# Arduino.net
KiCad netlist of a schematic drawn in Altium Designer
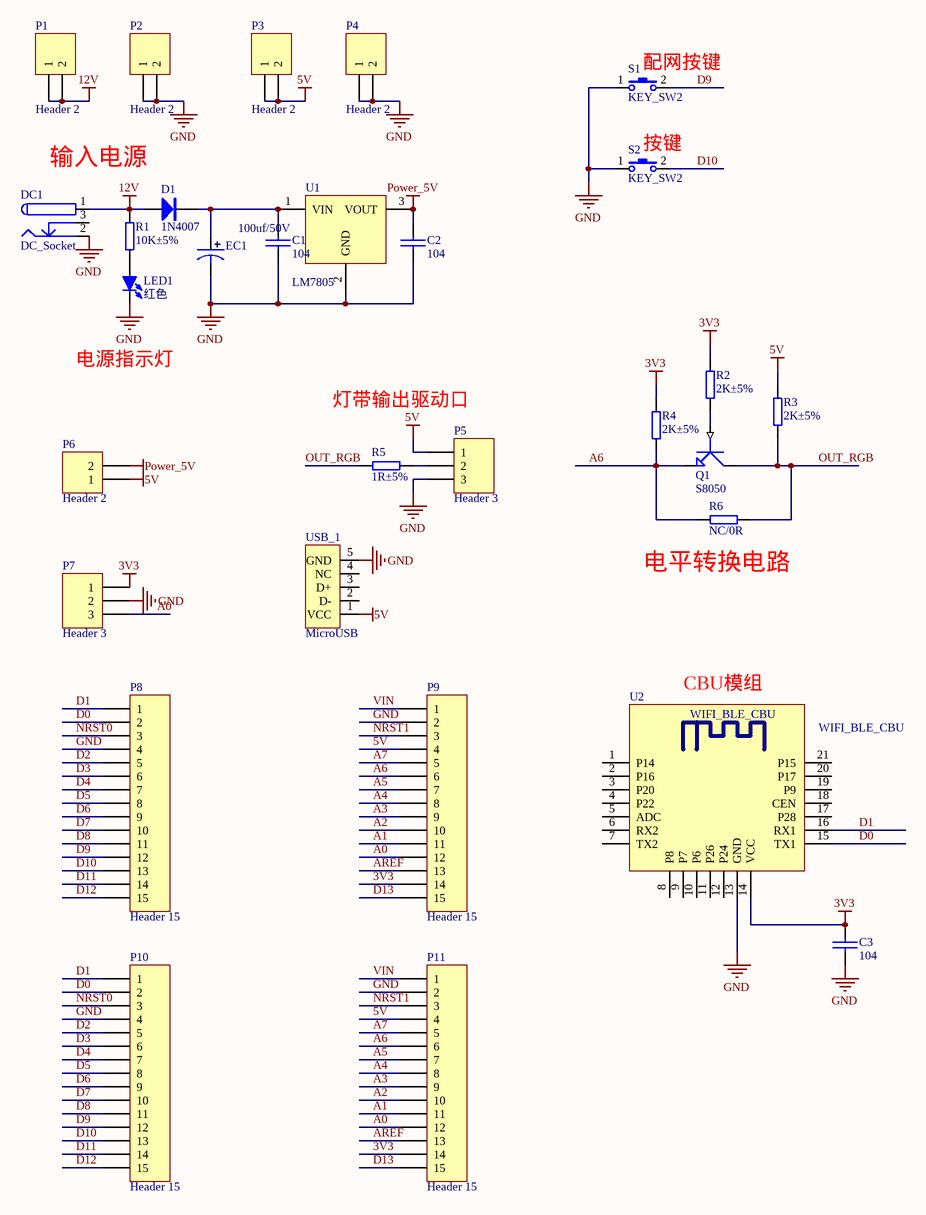
[diagram p0: Arduino幻彩灯带.SchDoc]

(export (version "E")
  (design (tool "Eeschema 10.0.6"))
  (components
    (comp (ref "C1")
      (value "104")
      (footprint "0805C")
      (description "无极性电容")
      (libsource (lib "电容") (part "CAP"))
    )
    (comp (ref "C2")
      (value "104")
      (footprint "0805C")
      (description "无极性电容")
      (libsource (lib "电容") (part "CAP"))
    )
    (comp (ref "C3")
      (value "104")
      (footprint "0805C")
      (description "无极性电容")
      (libsource (lib "电容") (part "CAP"))
    )
    (comp (ref "D1")
      (value "1N4007")
      (footprint "SMA")
      (description "整流二极管")
      (libsource (lib "二极管-整流桥") (part "1N4007"))
    )
    (comp (ref "DC1") (value "DC_Socket") (footprint "DC-005") (libsource (lib "电源插座") (part "DC_Socket")))
    (comp (ref "EC1")
      (value "100uf/50V")
      (footprint "DIP-EC3.5X8X11.5")
      (description "直插电解电容")
      (libsource (lib "电容") (part "DIP_ECAP"))
    )
    (comp (ref "LED1")
      (value "红色")
      (footprint "LED 0603R")
      (description "贴片LED")
      (libsource (lib "LED") (part "LED-SMD"))
    )
    (comp (ref "P1")
      (value "Header 2")
      (footprint "HDR1X2")
      (description "Header, 2-Pin")
      (fields (field (name "PUBLISHER") "Altium Limited"))
      (libsource (lib "Miscellaneous Connectors") (part "Header 2"))
    )
    (comp (ref "P2")
      (value "Header 2")
      (footprint "HDR1X2")
      (description "Header, 2-Pin")
      (fields (field (name "PUBLISHER") "Altium Limited"))
      (libsource (lib "Miscellaneous Connectors") (part "Header 2"))
    )
    (comp (ref "P3")
      (value "Header 2")
      (footprint "HDR1X2")
      (description "Header, 2-Pin")
      (fields (field (name "PUBLISHER") "Altium Limited"))
      (libsource (lib "Miscellaneous Connectors") (part "Header 2"))
    )
    (comp (ref "P4")
      (value "Header 2")
      (footprint "HDR1X2")
      (description "Header, 2-Pin")
      (fields (field (name "PUBLISHER") "Altium Limited"))
      (libsource (lib "Miscellaneous Connectors") (part "Header 2"))
    )
    (comp (ref "P5")
      (value "Header 3")
      (footprint "HDR1X3")
      (description "Header, 3-Pin")
      (fields (field (name "PUBLISHER") "Altium Limited"))
      (libsource (lib "Miscellaneous Connectors") (part "Header 3"))
    )
    (comp (ref "P6")
      (value "Header 2")
      (footprint "HDR1X2")
      (description "Header, 2-Pin")
      (fields (field (name "PUBLISHER") "Altium Limited"))
      (libsource (lib "") (part "Header 2_1"))
    )
    (comp (ref "P7")
      (value "Header 3")
      (footprint "HDR1X3")
      (description "Header, 3-Pin")
      (fields (field (name "PUBLISHER") "Altium Limited"))
      (libsource (lib "") (part "Header 3_1"))
    )
    (comp (ref "P8")
      (value "Header 15")
      (footprint "HDR1X15")
      (description "Header, 15-Pin")
      (fields (field (name "PUBLISHER") "Altium Limited"))
      (libsource (lib "Miscellaneous Connectors") (part "Header 15"))
    )
    (comp (ref "P9")
      (value "Header 15")
      (footprint "HDR1X15")
      (description "Header, 15-Pin")
      (fields (field (name "PUBLISHER") "Altium Limited"))
      (libsource (lib "Miscellaneous Connectors") (part "Header 15"))
    )
    (comp (ref "P10")
      (value "Header 15")
      (footprint "HDR1X15")
      (description "Header, 15-Pin")
      (fields (field (name "PUBLISHER") "Altium Limited"))
      (libsource (lib "Miscellaneous Connectors") (part "Header 15"))
    )
    (comp (ref "P11")
      (value "Header 15")
      (footprint "HDR1X15")
      (description "Header, 15-Pin")
      (fields (field (name "PUBLISHER") "Altium Limited"))
      (libsource (lib "Miscellaneous Connectors") (part "Header 15"))
    )
    (comp (ref "Q1")
      (value "S8050")
      (footprint "SOT-23-NPN")
      (description "NPN Transistor")
      (libsource (lib "小马元件库sch") (part "NPN"))
    )
    (comp (ref "R1") (value "10K±5%") (footprint "R0805") (libsource (lib "昊华元件库sch") (part "RES5")))
    (comp (ref "R2") (value "2K±5%") (footprint "R0603") (libsource (lib "昊华元件库sch") (part "RES5")))
    (comp (ref "R3") (value "2K±5%") (footprint "R0603") (libsource (lib "昊华元件库sch") (part "RES5")))
    (comp (ref "R4") (value "2K±5%") (footprint "R0603") (libsource (lib "昊华元件库sch") (part "RES5")))
    (comp (ref "R5") (value "1R±5%") (footprint "R0603") (libsource (lib "昊华元件库sch") (part "RES5")))
    (comp (ref "R6") (value "NC/0R") (footprint "R0603") (libsource (lib "昊华元件库sch") (part "RES5")))
    (comp (ref "S1") (value "KEY_SW2") (footprint "KEY4-SMD") (libsource (lib "小马元件库sch") (part "KEY_SW2")))
    (comp (ref "S2") (value "KEY_SW2") (footprint "KEY4-SMD") (libsource (lib "小马元件库sch") (part "KEY_SW2")))
    (comp (ref "U1") (value "LM7805") (footprint "TO252") (libsource (lib "电源芯片") (part "LM7805")))
    (comp (ref "U2")
      (value "WIFI_BLE_CBU")
      (footprint "WIFI_BLE_CBU")
      (description "Module")
      (libsource (lib "TYModeSchlib V03") (part "WIFI_BLE_CBU"))
    )
    (comp (ref "USB_1")
      (value "MicroUSB")
      (footprint "USB-micro_A")
      (libsource (lib "Game元件库") (part "MicroUSB"))
    )
  )
  (nets
    (net (code "1") (name "/A0") (class "Default")
      (node (ref "P11") (pin "12") (pinfunction "12_12") (pintype "passive"))
      (node (ref "P7") (pin "3") (pinfunction "3_3") (pintype "passive"))
      (node (ref "P9") (pin "12") (pinfunction "12_12") (pintype "passive"))
    )
    (net (code "2") (name "/A1") (class "Default")
      (node (ref "P11") (pin "11") (pinfunction "11_11") (pintype "passive"))
      (node (ref "P9") (pin "11") (pinfunction "11_11") (pintype "passive"))
    )
    (net (code "3") (name "/A2") (class "Default")
      (node (ref "P11") (pin "10") (pinfunction "10_10") (pintype "passive"))
      (node (ref "P9") (pin "10") (pinfunction "10_10") (pintype "passive"))
    )
    (net (code "4") (name "/A3") (class "Default")
      (node (ref "P11") (pin "9") (pinfunction "9_9") (pintype "passive"))
      (node (ref "P9") (pin "9") (pinfunction "9_9") (pintype "passive"))
    )
    (net (code "5") (name "/A4") (class "Default")
      (node (ref "P11") (pin "8") (pinfunction "8_8") (pintype "passive"))
      (node (ref "P9") (pin "8") (pinfunction "8_8") (pintype "passive"))
    )
    (net (code "6") (name "/A5") (class "Default")
      (node (ref "P11") (pin "7") (pinfunction "7_7") (pintype "passive"))
      (node (ref "P9") (pin "7") (pinfunction "7_7") (pintype "passive"))
    )
    (net (code "7") (name "/A6") (class "Default")
      (node (ref "P11") (pin "6") (pinfunction "6_6") (pintype "passive"))
      (node (ref "P9") (pin "6") (pinfunction "6_6") (pintype "passive"))
      (node (ref "Q1") (pin "1") (pinfunction "E_1") (pintype "passive"))
      (node (ref "R4") (pin "2") (pinfunction "2_2") (pintype "passive"))
      (node (ref "R6") (pin "1") (pinfunction "1_1") (pintype "passive"))
    )
    (net (code "8") (name "/A7") (class "Default")
      (node (ref "P11") (pin "5") (pinfunction "5_5") (pintype "passive"))
      (node (ref "P9") (pin "5") (pinfunction "5_5") (pintype "passive"))
    )
    (net (code "9") (name "/AREF") (class "Default")
      (node (ref "P11") (pin "13") (pinfunction "13_13") (pintype "passive"))
      (node (ref "P9") (pin "13") (pinfunction "13_13") (pintype "passive"))
    )
    (net (code "10") (name "/D0") (class "Default")
      (node (ref "P10") (pin "2") (pinfunction "2_2") (pintype "passive"))
      (node (ref "P8") (pin "2") (pinfunction "2_2") (pintype "passive"))
      (node (ref "U2") (pin "15") (pinfunction "TX1_15") (pintype "passive"))
    )
    (net (code "11") (name "/D1") (class "Default")
      (node (ref "P10") (pin "1") (pinfunction "1_1") (pintype "passive"))
      (node (ref "P8") (pin "1") (pinfunction "1_1") (pintype "passive"))
      (node (ref "U2") (pin "16") (pinfunction "RX1_16") (pintype "passive"))
    )
    (net (code "12") (name "/D2") (class "Default")
      (node (ref "P10") (pin "5") (pinfunction "5_5") (pintype "passive"))
      (node (ref "P8") (pin "5") (pinfunction "5_5") (pintype "passive"))
    )
    (net (code "13") (name "/D3") (class "Default")
      (node (ref "P10") (pin "6") (pinfunction "6_6") (pintype "passive"))
      (node (ref "P8") (pin "6") (pinfunction "6_6") (pintype "passive"))
    )
    (net (code "14") (name "/D4") (class "Default")
      (node (ref "P10") (pin "7") (pinfunction "7_7") (pintype "passive"))
      (node (ref "P8") (pin "7") (pinfunction "7_7") (pintype "passive"))
    )
    (net (code "15") (name "/D5") (class "Default")
      (node (ref "P10") (pin "8") (pinfunction "8_8") (pintype "passive"))
      (node (ref "P8") (pin "8") (pinfunction "8_8") (pintype "passive"))
    )
    (net (code "16") (name "/D6") (class "Default")
      (node (ref "P10") (pin "9") (pinfunction "9_9") (pintype "passive"))
      (node (ref "P8") (pin "9") (pinfunction "9_9") (pintype "passive"))
    )
    (net (code "17") (name "/D7") (class "Default")
      (node (ref "P10") (pin "10") (pinfunction "10_10") (pintype "passive"))
      (node (ref "P8") (pin "10") (pinfunction "10_10") (pintype "passive"))
    )
    (net (code "18") (name "/D8") (class "Default")
      (node (ref "P10") (pin "11") (pinfunction "11_11") (pintype "passive"))
      (node (ref "P8") (pin "11") (pinfunction "11_11") (pintype "passive"))
    )
    (net (code "19") (name "/D9") (class "Default")
      (node (ref "P10") (pin "12") (pinfunction "12_12") (pintype "passive"))
      (node (ref "P8") (pin "12") (pinfunction "12_12") (pintype "passive"))
      (node (ref "S1") (pin "2") (pinfunction "2_2") (pintype "passive"))
    )
    (net (code "20") (name "/D10") (class "Default")
      (node (ref "P10") (pin "13") (pinfunction "13_13") (pintype "passive"))
      (node (ref "P8") (pin "13") (pinfunction "13_13") (pintype "passive"))
      (node (ref "S2") (pin "2") (pinfunction "2_2") (pintype "passive"))
    )
    (net (code "21") (name "/D11") (class "Default")
      (node (ref "P10") (pin "14") (pinfunction "14_14") (pintype "passive"))
      (node (ref "P8") (pin "14") (pinfunction "14_14") (pintype "passive"))
    )
    (net (code "22") (name "/D12") (class "Default")
      (node (ref "P10") (pin "15") (pinfunction "15_15") (pintype "passive"))
      (node (ref "P8") (pin "15") (pinfunction "15_15") (pintype "passive"))
    )
    (net (code "23") (name "/D13") (class "Default")
      (node (ref "P11") (pin "15") (pinfunction "15_15") (pintype "passive"))
      (node (ref "P9") (pin "15") (pinfunction "15_15") (pintype "passive"))
    )
    (net (code "24") (name "/NRST0") (class "Default")
      (node (ref "P10") (pin "3") (pinfunction "3_3") (pintype "passive"))
      (node (ref "P8") (pin "3") (pinfunction "3_3") (pintype "passive"))
    )
    (net (code "25") (name "/NRST1") (class "Default")
      (node (ref "P11") (pin "3") (pinfunction "3_3") (pintype "passive"))
      (node (ref "P9") (pin "3") (pinfunction "3_3") (pintype "passive"))
    )
    (net (code "26") (name "/OUT_RGB") (class "Default")
      (node (ref "Q1") (pin "3") (pinfunction "C_3") (pintype "passive"))
      (node (ref "R3") (pin "2") (pinfunction "2_2") (pintype "passive"))
      (node (ref "R5") (pin "1") (pinfunction "1_1") (pintype "passive"))
      (node (ref "R6") (pin "2") (pinfunction "2_2") (pintype "passive"))
    )
    (net (code "27") (name "/VIN") (class "Default")
      (node (ref "P11") (pin "1") (pinfunction "1_1") (pintype "passive"))
      (node (ref "P9") (pin "1") (pinfunction "1_1") (pintype "passive"))
    )
    (net (code "28") (name "3V3") (class "Default")
      (node (ref "C3") (pin "1") (pinfunction "1_1") (pintype "passive"))
      (node (ref "P11") (pin "14") (pinfunction "14_14") (pintype "passive"))
      (node (ref "P7") (pin "1") (pinfunction "1_1") (pintype "passive"))
      (node (ref "P9") (pin "14") (pinfunction "14_14") (pintype "passive"))
      (node (ref "R2") (pin "1") (pinfunction "1_1") (pintype "passive"))
      (node (ref "R4") (pin "1") (pinfunction "1_1") (pintype "passive"))
      (node (ref "U2") (pin "14") (pinfunction "VCC_14") (pintype "passive"))
    )
    (net (code "29") (name "5V") (class "Default")
      (node (ref "P11") (pin "4") (pinfunction "4_4") (pintype "passive"))
      (node (ref "P3") (pin "1") (pinfunction "1_1") (pintype "passive"))
      (node (ref "P3") (pin "2") (pinfunction "2_2") (pintype "passive"))
      (node (ref "P5") (pin "1") (pinfunction "1_1") (pintype "passive"))
      (node (ref "P6") (pin "1") (pinfunction "1_1") (pintype "passive"))
      (node (ref "P9") (pin "4") (pinfunction "4_4") (pintype "passive"))
      (node (ref "R3") (pin "1") (pinfunction "1_1") (pintype "passive"))
      (node (ref "USB_1") (pin "1") (pinfunction "VCC_1") (pintype "passive"))
    )
    (net (code "30") (name "12V") (class "Default")
      (node (ref "D1") (pin "1") (pinfunction "A_1") (pintype "passive"))
      (node (ref "DC1") (pin "1") (pinfunction "1_1") (pintype "power_in"))
      (node (ref "P1") (pin "1") (pinfunction "1_1") (pintype "passive"))
      (node (ref "P1") (pin "2") (pinfunction "2_2") (pintype "passive"))
      (node (ref "R1") (pin "1") (pinfunction "1_1") (pintype "passive"))
    )
    (net (code "31") (name "GND") (class "Default")
      (node (ref "C1") (pin "1") (pinfunction "1_1") (pintype "passive"))
      (node (ref "C2") (pin "1") (pinfunction "1_1") (pintype "passive"))
      (node (ref "C3") (pin "2") (pinfunction "2_2") (pintype "passive"))
      (node (ref "DC1") (pin "2") (pinfunction "2_2") (pintype "power_in"))
      (node (ref "EC1") (pin "2") (pinfunction "2_2") (pintype "passive"))
      (node (ref "LED1") (pin "2") (pinfunction "K_2") (pintype "passive"))
      (node (ref "P10") (pin "4") (pinfunction "4_4") (pintype "passive"))
      (node (ref "P11") (pin "2") (pinfunction "2_2") (pintype "passive"))
      (node (ref "P2") (pin "1") (pinfunction "1_1") (pintype "passive"))
      (node (ref "P2") (pin "2") (pinfunction "2_2") (pintype "passive"))
      (node (ref "P4") (pin "1") (pinfunction "1_1") (pintype "passive"))
      (node (ref "P4") (pin "2") (pinfunction "2_2") (pintype "passive"))
      (node (ref "P5") (pin "3") (pinfunction "3_3") (pintype "passive"))
      (node (ref "P7") (pin "2") (pinfunction "2_2") (pintype "passive"))
      (node (ref "P8") (pin "4") (pinfunction "4_4") (pintype "passive"))
      (node (ref "P9") (pin "2") (pinfunction "2_2") (pintype "passive"))
      (node (ref "S1") (pin "1") (pinfunction "1_1") (pintype "passive"))
      (node (ref "S2") (pin "1") (pinfunction "1_1") (pintype "passive"))
      (node (ref "U1") (pin "2") (pinfunction "GND_2") (pintype "passive"))
      (node (ref "U2") (pin "13") (pinfunction "GND_13") (pintype "passive"))
      (node (ref "USB_1") (pin "5") (pinfunction "GND_5") (pintype "passive"))
    )
    (net (code "32") (name "Net-(D1-K)") (class "Default")
      (node (ref "C1") (pin "2") (pinfunction "2_2") (pintype "passive"))
      (node (ref "D1") (pin "2") (pinfunction "K_2") (pintype "passive"))
      (node (ref "EC1") (pin "1") (pinfunction "1_1") (pintype "passive"))
      (node (ref "U1") (pin "1") (pinfunction "VIN_1") (pintype "passive"))
    )
    (net (code "33") (name "Net-(LED1-A)") (class "Default")
      (node (ref "LED1") (pin "1") (pinfunction "A_1") (pintype "passive"))
      (node (ref "R1") (pin "2") (pinfunction "2_2") (pintype "passive"))
    )
    (net (code "34") (name "Net-(P5-Pad2)") (class "Default")
      (node (ref "P5") (pin "2") (pinfunction "2_2") (pintype "passive"))
      (node (ref "R5") (pin "2") (pinfunction "2_2") (pintype "passive"))
    )
    (net (code "35") (name "Net-(Q1-B)") (class "Default")
      (node (ref "Q1") (pin "2") (pinfunction "B_2") (pintype "input"))
      (node (ref "R2") (pin "2") (pinfunction "2_2") (pintype "passive"))
    )
    (net (code "36") (name "Power_5V") (class "Default")
      (node (ref "C2") (pin "2") (pinfunction "2_2") (pintype "passive"))
      (node (ref "P6") (pin "2") (pinfunction "2_2") (pintype "passive"))
      (node (ref "U1") (pin "3") (pinfunction "VOUT_3") (pintype "passive"))
    )
    (net (code "37") (name "unconnected-(DC1-Pad3)") (class "Default")
      (node (ref "DC1") (pin "3") (pinfunction "3_3") (pintype "power_in"))
    )
    (net (code "38") (name "unconnected-(U2-ADC-Pad5)") (class "Default")
      (node (ref "U2") (pin "5") (pinfunction "ADC_5") (pintype "passive"))
    )
    (net (code "39") (name "unconnected-(U2-CEN-Pad18)") (class "Default")
      (node (ref "U2") (pin "18") (pinfunction "CEN_18") (pintype "passive"))
    )
    (net (code "40") (name "unconnected-(U2-P6-Pad10)") (class "Default")
      (node (ref "U2") (pin "10") (pinfunction "P6_10") (pintype "passive"))
    )
    (net (code "41") (name "unconnected-(U2-P7-Pad9)") (class "Default")
      (node (ref "U2") (pin "9") (pinfunction "P7_9") (pintype "passive"))
    )
    (net (code "42") (name "unconnected-(U2-P8-Pad8)") (class "Default")
      (node (ref "U2") (pin "8") (pinfunction "P8_8") (pintype "passive"))
    )
    (net (code "43") (name "unconnected-(U2-P9-Pad19)") (class "Default")
      (node (ref "U2") (pin "19") (pinfunction "P9_19") (pintype "passive"))
    )
    (net (code "44") (name "unconnected-(U2-P14-Pad1)") (class "Default")
      (node (ref "U2") (pin "1") (pinfunction "P14_1") (pintype "passive"))
    )
    (net (code "45") (name "unconnected-(U2-P15-Pad21)") (class "Default")
      (node (ref "U2") (pin "21") (pinfunction "P15_21") (pintype "passive"))
    )
    (net (code "46") (name "unconnected-(U2-P16-Pad2)") (class "Default")
      (node (ref "U2") (pin "2") (pinfunction "P16_2") (pintype "passive"))
    )
    (net (code "47") (name "unconnected-(U2-P17-Pad20)") (class "Default")
      (node (ref "U2") (pin "20") (pinfunction "P17_20") (pintype "passive"))
    )
    (net (code "48") (name "unconnected-(U2-P20-Pad3)") (class "Default")
      (node (ref "U2") (pin "3") (pinfunction "P20_3") (pintype "passive"))
    )
    (net (code "49") (name "unconnected-(U2-P22-Pad4)") (class "Default")
      (node (ref "U2") (pin "4") (pinfunction "P22_4") (pintype "passive"))
    )
    (net (code "50") (name "unconnected-(U2-P24-Pad12)") (class "Default")
      (node (ref "U2") (pin "12") (pinfunction "P24_12") (pintype "passive"))
    )
    (net (code "51") (name "unconnected-(U2-P26-Pad11)") (class "Default")
      (node (ref "U2") (pin "11") (pinfunction "P26_11") (pintype "passive"))
    )
    (net (code "52") (name "unconnected-(U2-P28-Pad17)") (class "Default")
      (node (ref "U2") (pin "17") (pinfunction "P28_17") (pintype "passive"))
    )
    (net (code "53") (name "unconnected-(U2-RX2-Pad6)") (class "Default")
      (node (ref "U2") (pin "6") (pinfunction "RX2_6") (pintype "passive"))
    )
    (net (code "54") (name "unconnected-(U2-TX2-Pad7)") (class "Default")
      (node (ref "U2") (pin "7") (pinfunction "TX2_7") (pintype "passive"))
    )
    (net (code "55") (name "unconnected-(USB_1-D+-Pad3)") (class "Default")
      (node (ref "USB_1") (pin "3") (pinfunction "D+_3") (pintype "passive"))
    )
    (net (code "56") (name "unconnected-(USB_1-D--Pad2)") (class "Default")
      (node (ref "USB_1") (pin "2") (pinfunction "D-_2") (pintype "passive"))
    )
    (net (code "57") (name "unconnected-(USB_1-NC-Pad4)") (class "Default")
      (node (ref "USB_1") (pin "4") (pinfunction "NC_4") (pintype "passive"))
    )
  )
)
